# RS_232.net
KiCad netlist of a schematic drawn in Altium Designer
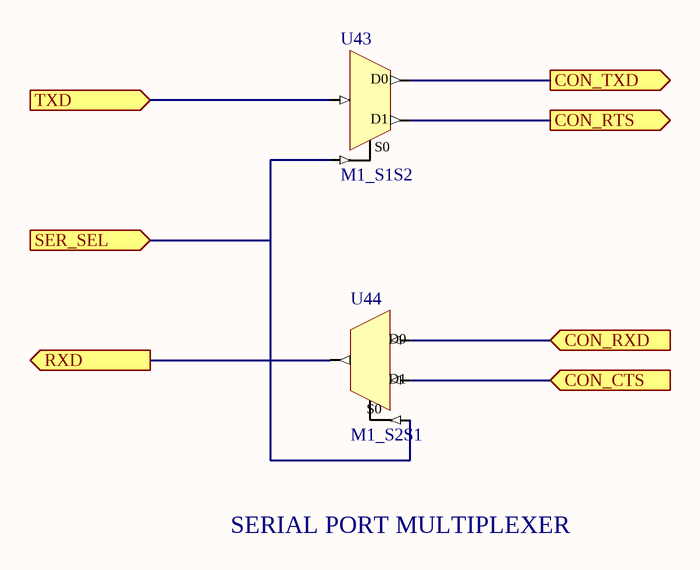
[diagram p0: RS_232.SchDoc]

(export (version "E")
  (design (tool "Eeschema 10.0.6"))
  (components
    (comp (ref "U43")
      (value "M1_S1S2")
      (description "1x1-Single Wire to 2x1-Single Wire Multiplexer (Demultiplex)")
      (fields (field (name "PUBLISHER") "Altium Limited"))
      (libsource (lib "FPGA Generic") (part "M1_S1S2"))
    )
    (comp (ref "U44")
      (value "M1_S2S1")
      (description "2x1-Single Wire to 1x1-Single Wire Multiplexer")
      (fields (field (name "PUBLISHER") "Altium Limited"))
      (libsource (lib "FPGA Generic") (part "M1_S2S1"))
    )
  )
  (nets
    (net (code "1") (name "/CON_CTS") (class "Default")
      (node (ref "U44") (pin "D1") (pinfunction "D1_D1") (pintype "input"))
    )
    (net (code "2") (name "/CON_RTS") (class "Default")
      (node (ref "U43") (pin "D1") (pinfunction "D1_D1") (pintype "output"))
    )
    (net (code "3") (name "/CON_RXD") (class "Default")
      (node (ref "U44") (pin "D0") (pinfunction "D0_D0") (pintype "input"))
    )
    (net (code "4") (name "/CON_TXD") (class "Default")
      (node (ref "U43") (pin "D0") (pinfunction "D0_D0") (pintype "output"))
    )
    (net (code "5") (name "/RXD") (class "Default")
      (node (ref "U44") (pin "O") (pinfunction "O_O") (pintype "output"))
    )
    (net (code "7") (name "/SER_SEL") (class "Default")
      (node (ref "U43") (pin "S0") (pinfunction "S0_S0") (pintype "input"))
      (node (ref "U44") (pin "S0") (pinfunction "S0_S0") (pintype "input"))
    )
    (net (code "8") (name "/TXD") (class "Default")
      (node (ref "U43") (pin "O") (pinfunction "O_O") (pintype "input"))
    )
  )
)
